# YOTSUBA__Y_Z_ver_1_0.net
KiCad netlist of a schematic drawn in EAGLE
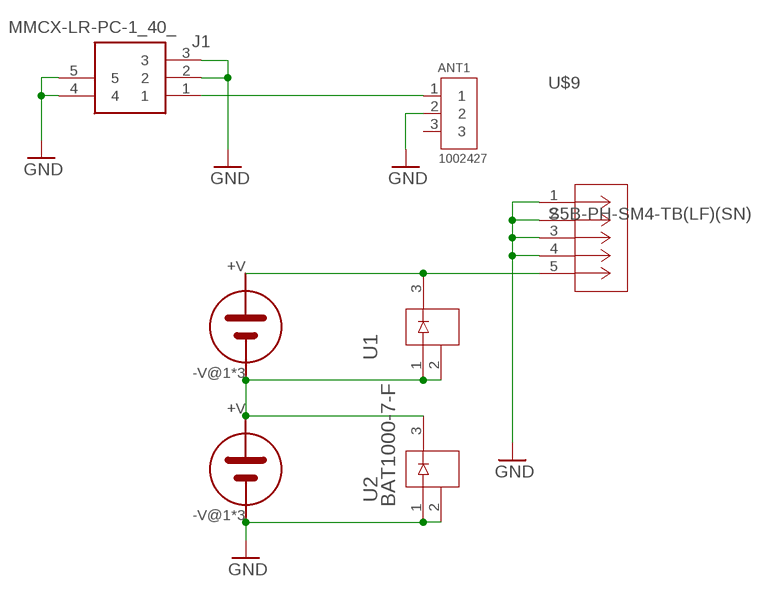
[diagram p0: schematic, sheet 1]

(export (version "E")
  (design (tool "Eeschema 10.0.6"))
  (components
    (comp (ref "ANT1")
      (value "1002427")
      (footprint "eagle-import:ANTENNA_1002427")
      (fields (field (name "DIGI-KEY_PART_NUMBER") "478-1002427TR-ND") (field (name "MF") "Ethertronics/AVX"))
      (libsource (lib "eagle-import") (part "1002427"))
    )
    (comp (ref "J1")
      (value "MMCX-LR-PC-1_40_")
      (footprint "eagle-import:MMCXLRPC140")
      (fields
        (field (name "MANUFACTURER_PART_NUMBER") "MMCX-LR-PC-1(40)")
        (field (name "MOUSER_PART_NUMBER") "798-MMCX-LR-PC-1(40)")
      )
      (libsource (lib "eagle-import") (part "MMCX-LR-PC-1_40_"))
    )
    (comp (ref "U$2")
      (value "3G30A")
      (footprint "eagle-import:SOLAR_3G30A")
      (libsource (lib "eagle-import") (part "3G30A"))
    )
    (comp (ref "U$3")
      (value "3G30A")
      (footprint "eagle-import:SOLAR_3G30A")
      (libsource (lib "eagle-import") (part "3G30A"))
    )
    (comp (ref "U$9")
      (value "S5B-PH-SM4-TB(LF)(SN)")
      (footprint "eagle-import:CONN_S5B-PH-SM4-TB_JST")
      (fields (field (name "COPYRIGHT") "Copyright (C) 2023 Ultra Librarian. All rights reserved."))
      (libsource (lib "eagle-import") (part "S5B-PH-SM4-TB(LF)(SN)"))
    )
    (comp (ref "U1")
      (value "BAT1000-7-F")
      (footprint "eagle-import:SOT23_BAT_DIO")
      (fields (field (name "COPYRIGHT") "Copyright (C) 2023 Ultra Librarian. All rights reserved."))
      (libsource (lib "eagle-import") (part "BAT1000-7-F"))
    )
    (comp (ref "U2")
      (value "BAT1000-7-F")
      (footprint "eagle-import:SOT23_BAT_DIO")
      (fields (field (name "COPYRIGHT") "Copyright (C) 2023 Ultra Librarian. All rights reserved."))
      (libsource (lib "eagle-import") (part "BAT1000-7-F"))
    )
  )
  (nets
    (net (code "1") (name "GND") (class "Default")
      (node (ref "ANT1") (pin "2") (pinfunction "2_2") (pintype "passive"))
      (node (ref "J1") (pin "2") (pinfunction "2_2") (pintype "bidirectional"))
      (node (ref "J1") (pin "3") (pinfunction "3_3") (pintype "bidirectional"))
      (node (ref "J1") (pin "4") (pinfunction "4_4") (pintype "bidirectional"))
      (node (ref "J1") (pin "5") (pinfunction "5_5") (pintype "bidirectional"))
      (node (ref "U$3") (pin "-V@1") (pinfunction "-V_-V@1") (pintype "bidirectional"))
      (node (ref "U$3") (pin "-V@2") (pinfunction "-V_-V@2") (pintype "bidirectional"))
      (node (ref "U$3") (pin "-V@3") (pinfunction "-V_-V@3") (pintype "bidirectional"))
      (node (ref "U$9") (pin "1") (pinfunction "1_1") (pintype "passive"))
      (node (ref "U$9") (pin "2") (pinfunction "2_2") (pintype "passive"))
      (node (ref "U$9") (pin "3") (pinfunction "3_3") (pintype "passive"))
      (node (ref "U$9") (pin "4") (pinfunction "4_4") (pintype "passive"))
      (node (ref "U2") (pin "1") (pinfunction "1_1") (pintype "passive"))
      (node (ref "U2") (pin "2") (pinfunction "2_2") (pintype "passive"))
    )
    (net (code "2") (name "Net-(ANT1-Pad1)") (class "Default")
      (node (ref "ANT1") (pin "1") (pinfunction "1_1") (pintype "passive"))
      (node (ref "J1") (pin "1") (pinfunction "1_1") (pintype "bidirectional"))
    )
    (net (code "3") (name "Net-(U$2--V-Pad-V@1)") (class "Default")
      (node (ref "U$2") (pin "-V@1") (pinfunction "-V_-V@1") (pintype "bidirectional"))
      (node (ref "U$2") (pin "-V@2") (pinfunction "-V_-V@2") (pintype "bidirectional"))
      (node (ref "U$2") (pin "-V@3") (pinfunction "-V_-V@3") (pintype "bidirectional"))
      (node (ref "U$3") (pin "+V") (pinfunction "+V_+V") (pintype "bidirectional"))
      (node (ref "U1") (pin "1") (pinfunction "1_1") (pintype "passive"))
      (node (ref "U1") (pin "2") (pinfunction "2_2") (pintype "passive"))
      (node (ref "U2") (pin "3") (pinfunction "3_3") (pintype "passive"))
    )
    (net (code "4") (name "Net-(U$2-Pad+V)") (class "Default")
      (node (ref "U$2") (pin "+V") (pinfunction "+V_+V") (pintype "bidirectional"))
      (node (ref "U$9") (pin "5") (pinfunction "5_5") (pintype "passive"))
      (node (ref "U1") (pin "3") (pinfunction "3_3") (pintype "passive"))
    )
    (net (code "5") (name "unconnected-(ANT1-Pad3)") (class "Default")
      (node (ref "ANT1") (pin "3") (pinfunction "3_3") (pintype "passive"))
    )
  )
)
